# 01.net
KiCad netlist of a schematic drawn in EasyEDA Pro
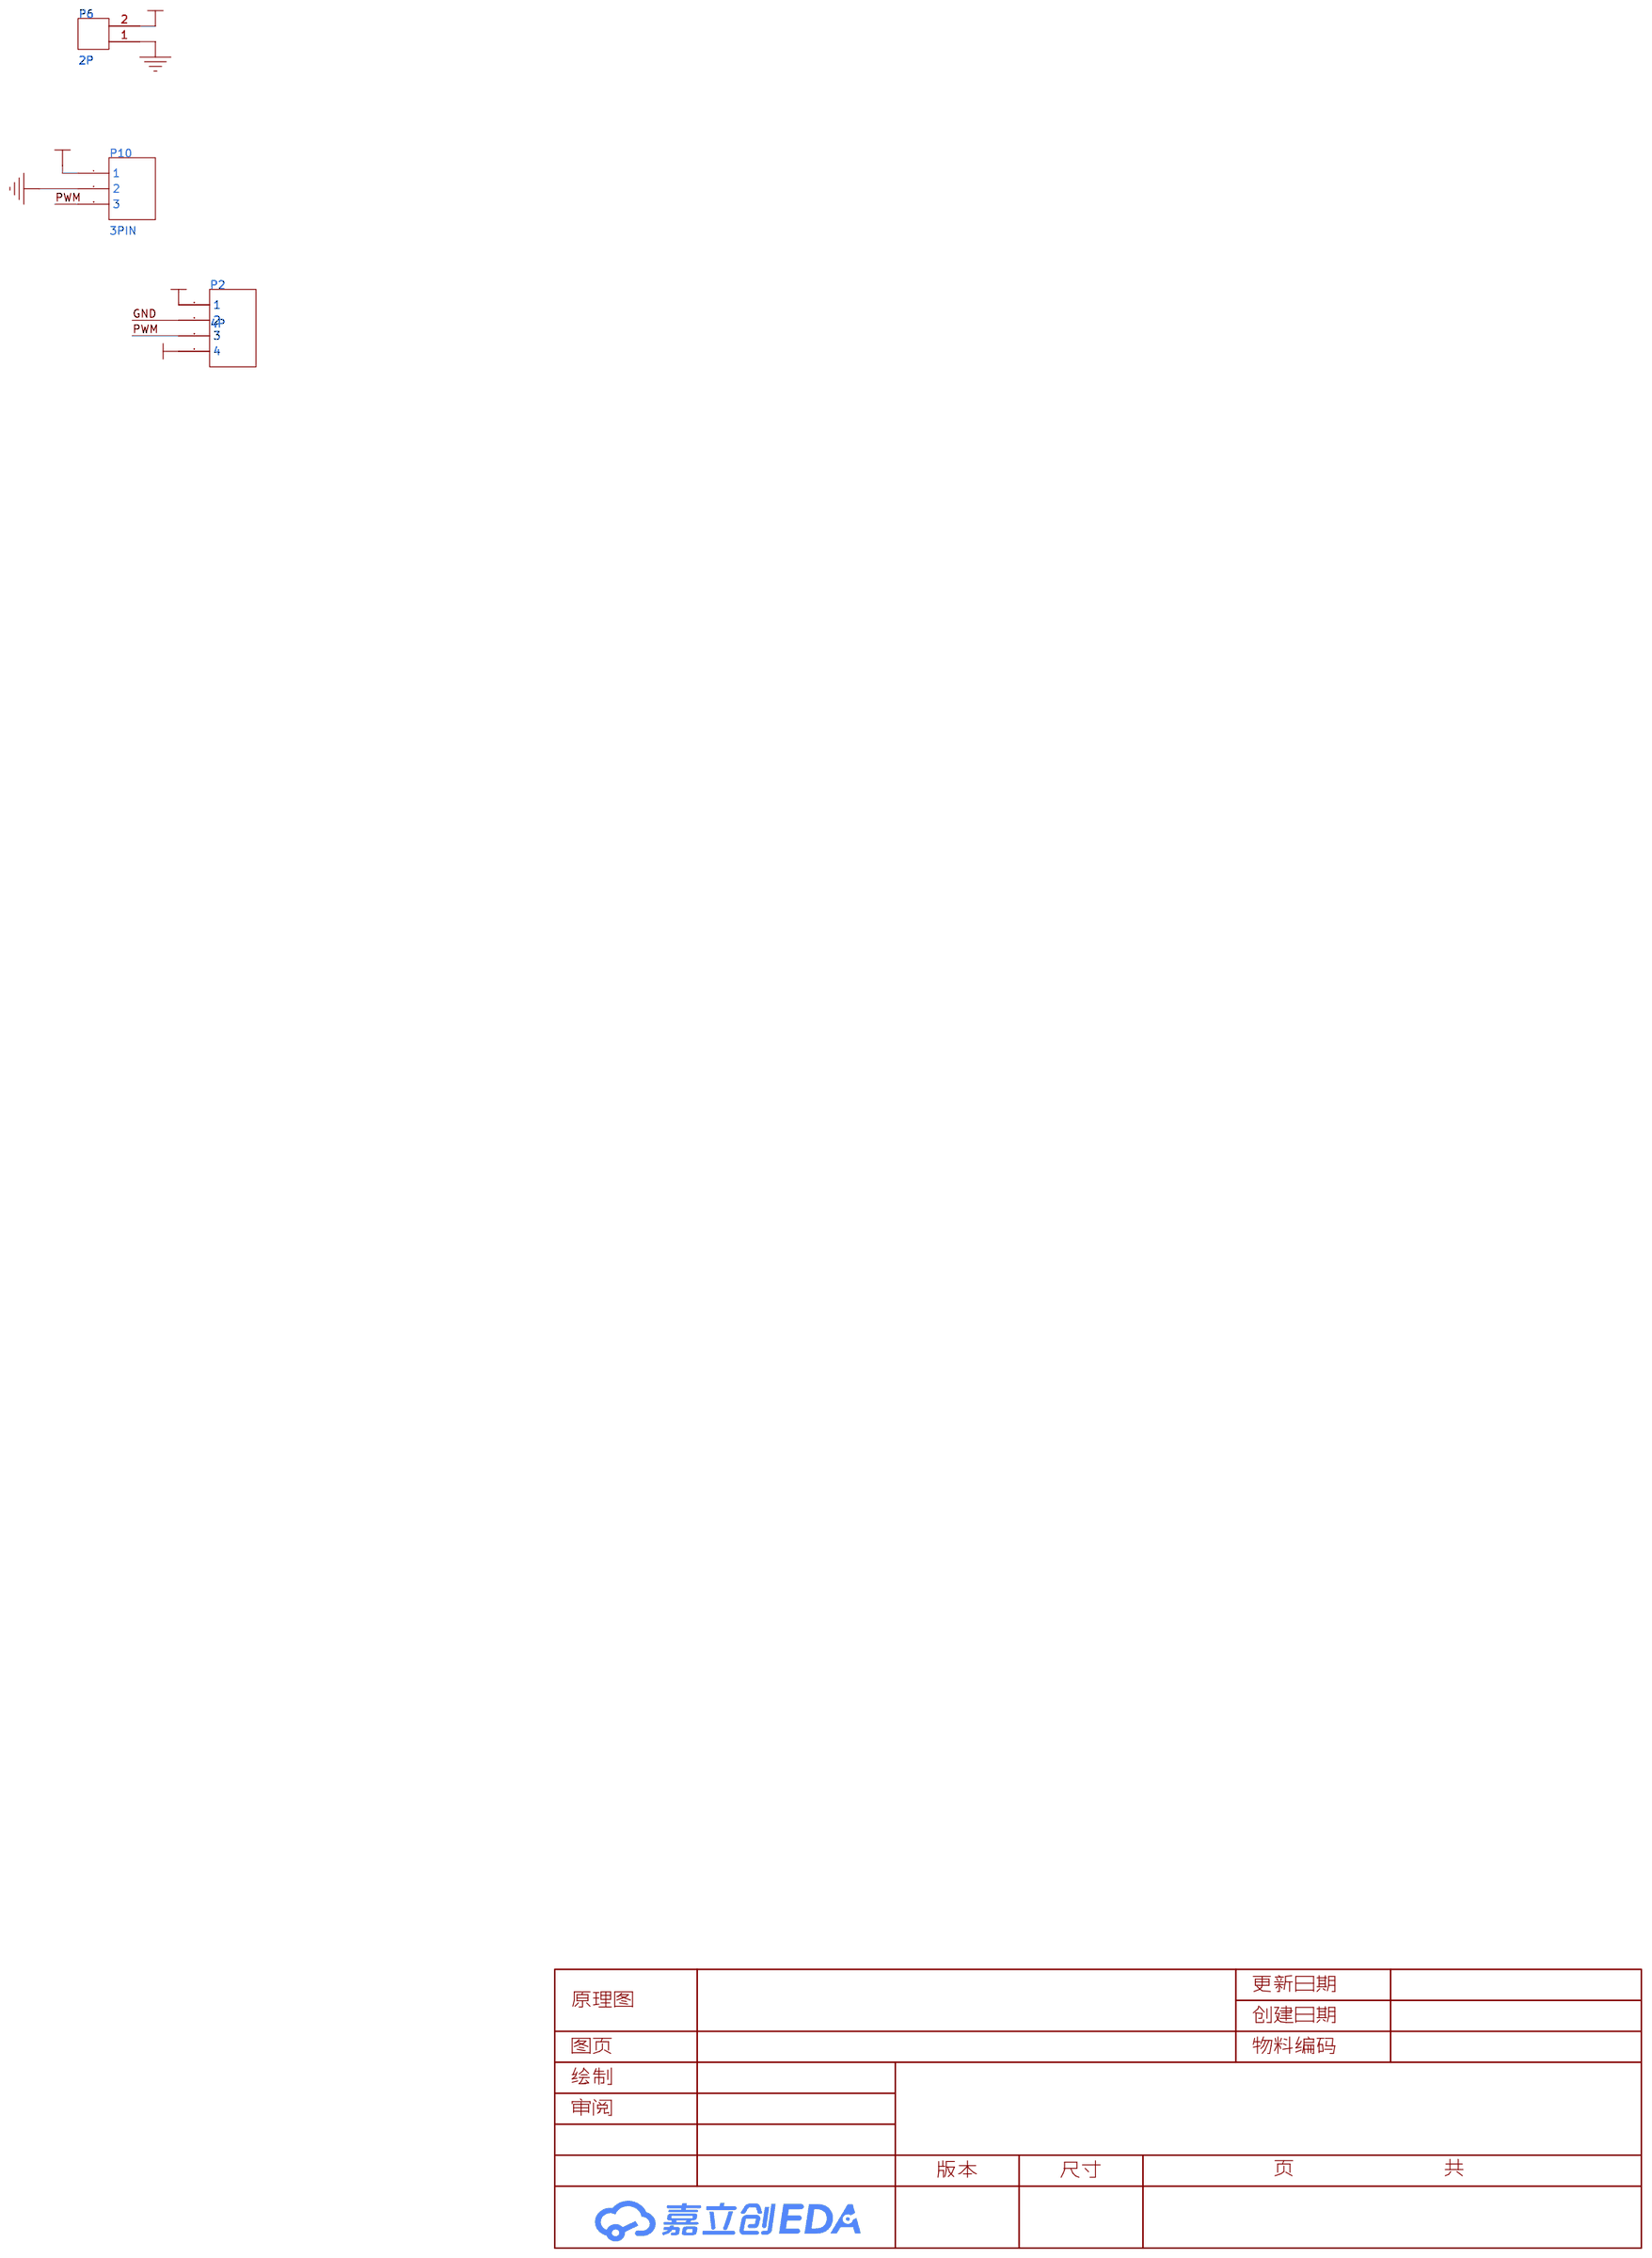
[diagram p0: schematic sheet]

(export (version "E")
  (design (tool "Eeschema 10.0.6"))
  (components
    (comp (ref "P2") (value "4P") (footprint "easyedapro:SIP4") (libsource (lib "easyedapro") (part "4P")))
    (comp (ref "P6")
      (value "2P")
      (footprint "easyedapro:HDR1X2_P")
      (libsource (lib "easyedapro") (part "2P"))
    )
    (comp (ref "P10")
      (value "3PIN")
      (footprint "easyedapro:HDR1X3_P")
      (libsource (lib "easyedapro") (part "3P"))
    )
  )
  (nets
    (net (code "1") (name "/PWM") (class "Default")
      (node (ref "P10") (pin "3") (pinfunction "3_3") (pintype "unspecified"))
      (node (ref "P2") (pin "3") (pinfunction "3_3") (pintype "unspecified"))
    )
    (net (code "2") (name "12V") (class "Default")
      (node (ref "P10") (pin "1") (pinfunction "1_1") (pintype "unspecified"))
      (node (ref "P2") (pin "4") (pinfunction "4_4") (pintype "unspecified"))
    )
    (net (code "3") (name "48V") (class "Default")
      (node (ref "P2") (pin "1") (pinfunction "1_1") (pintype "unspecified"))
      (node (ref "P6") (pin "2") (pintype "unspecified"))
    )
    (net (code "4") (name "GND") (class "Default")
      (node (ref "P10") (pin "2") (pinfunction "2_2") (pintype "unspecified"))
      (node (ref "P2") (pin "2") (pinfunction "2_2") (pintype "unspecified"))
      (node (ref "P6") (pin "1") (pintype "unspecified"))
    )
  )
)
